# schaltplan.net
KiCad netlist of a schematic drawn in EAGLE
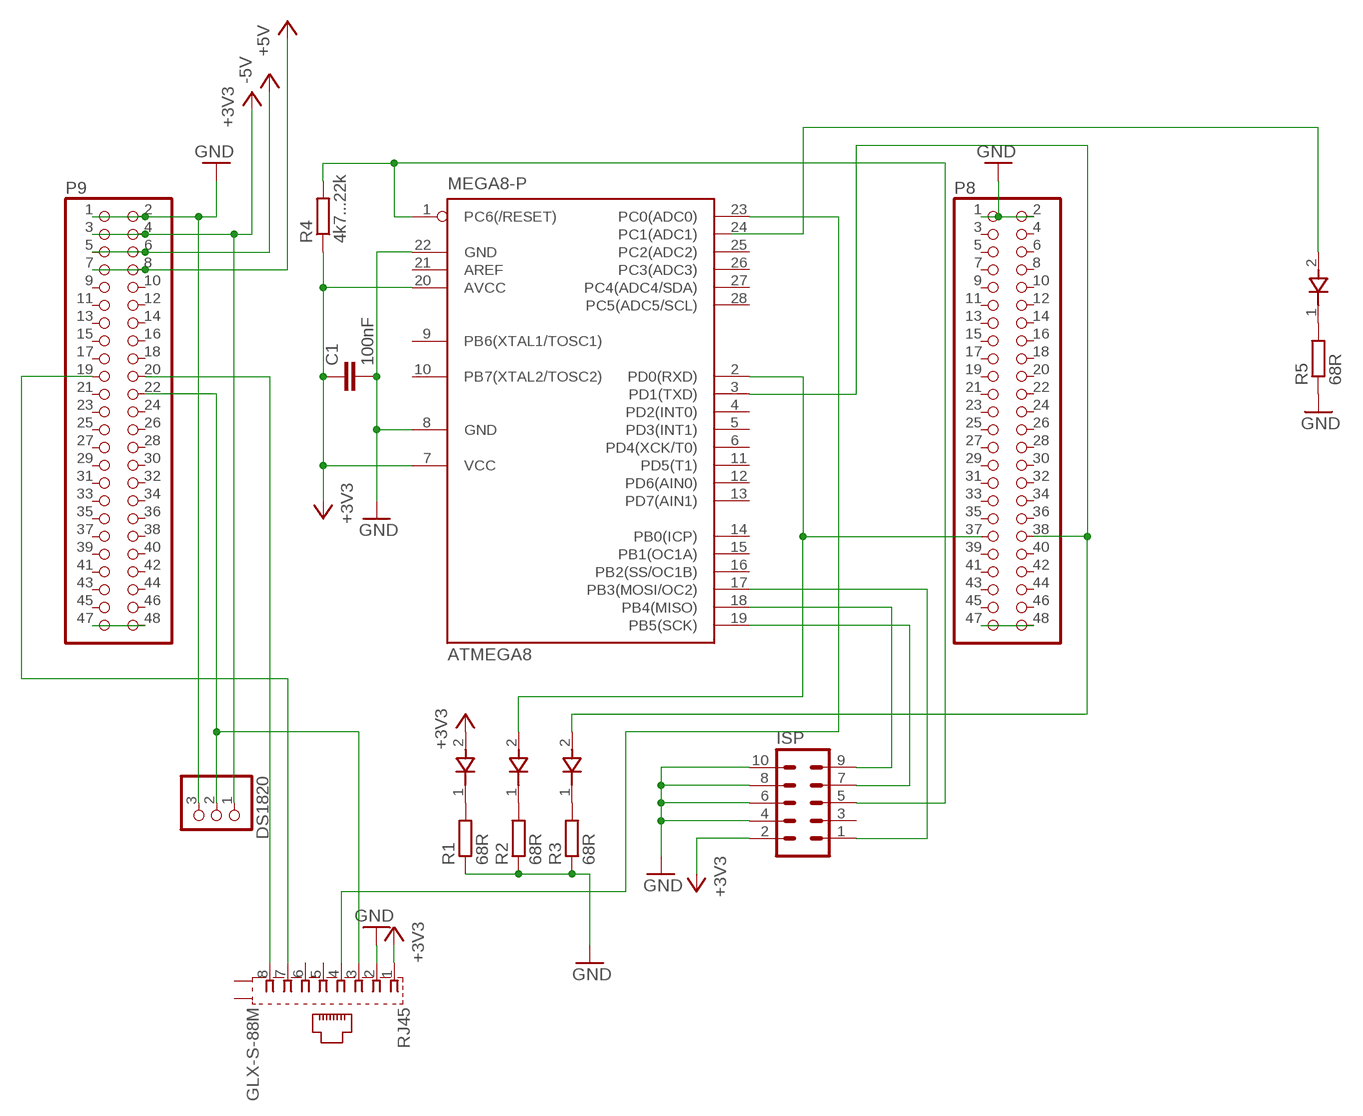
[diagram p0: schematic, sheet 1]

(export (version "E")
  (design (tool "Eeschema 10.0.6"))
  (components
    (comp (ref "ATMEGA8")
      (value "MEGA8-P")
      (footprint "eagle-import:DIL28-3")
      (libsource (lib "eagle-import") (part "MEGA8-P"))
    )
    (comp (ref "C1")
      (value "100nF")
      (footprint "eagle-import:C0805")
      (libsource (lib "eagle-import") (part "C-EUC0805"))
    )
    (comp (ref "DS1820")
      (value "PINHD-1X3")
      (footprint "eagle-import:1X03")
      (libsource (lib "eagle-import") (part "PINHD-1X3"))
    )
    (comp (ref "ISP")
      (value "ML10")
      (footprint "eagle-import:ML10")
      (libsource (lib "eagle-import") (part "ML10"))
    )
    (comp (ref "P8")
      (value "PINHD-2X24")
      (footprint "eagle-import:2X24")
      (libsource (lib "eagle-import") (part "PINHD-2X24"))
    )
    (comp (ref "P9")
      (value "PINHD-2X24")
      (footprint "eagle-import:2X24")
      (libsource (lib "eagle-import") (part "PINHD-2X24"))
    )
    (comp (ref "R1")
      (value "68R")
      (footprint "eagle-import:R1206")
      (libsource (lib "eagle-import") (part "R-EU_R1206"))
    )
    (comp (ref "R2")
      (value "68R")
      (footprint "eagle-import:R1206")
      (libsource (lib "eagle-import") (part "R-EU_R1206"))
    )
    (comp (ref "R3")
      (value "68R")
      (footprint "eagle-import:R1206")
      (libsource (lib "eagle-import") (part "R-EU_R1206"))
    )
    (comp (ref "R4")
      (value "4k7...22k")
      (footprint "eagle-import:R1206")
      (libsource (lib "eagle-import") (part "R-EU_R1206"))
    )
    (comp (ref "R5")
      (value "68R")
      (footprint "eagle-import:R1206")
      (libsource (lib "eagle-import") (part "R-EU_R1206"))
    )
    (comp (ref "RJ45")
      (value "GLX-S-88M")
      (footprint "eagle-import:GLX-S-88M")
      (libsource (lib "eagle-import") (part "GLX-S-88M"))
    )
    (comp (ref "U$1")
      (value "LOL_LED")
      (footprint "eagle-import:LOL_LED")
      (libsource (lib "eagle-import") (part "LOL_LED"))
    )
    (comp (ref "U$2")
      (value "LOL_LED")
      (footprint "eagle-import:LOL_LED")
      (libsource (lib "eagle-import") (part "LOL_LED"))
    )
    (comp (ref "U$3")
      (value "LOL_LED")
      (footprint "eagle-import:LOL_LED")
      (libsource (lib "eagle-import") (part "LOL_LED"))
    )
    (comp (ref "U$4")
      (value "LOL_LED")
      (footprint "eagle-import:LOL_LED")
      (libsource (lib "eagle-import") (part "LOL_LED"))
    )
  )
  (nets
    (net (code "1") (name "+3V3") (class "Default")
      (node (ref "ATMEGA8") (pin "20") (pinfunction "AVCC_20") (pintype "power_in"))
      (node (ref "ATMEGA8") (pin "7") (pinfunction "VCC_7") (pintype "power_in"))
      (node (ref "C1") (pin "1") (pinfunction "1_1") (pintype "passive"))
      (node (ref "DS1820") (pin "1") (pinfunction "1_1") (pintype "passive"))
      (node (ref "ISP") (pin "2") (pinfunction "2_2") (pintype "passive"))
      (node (ref "P9") (pin "3") (pinfunction "3_3") (pintype "passive"))
      (node (ref "P9") (pin "4") (pinfunction "4_4") (pintype "passive"))
      (node (ref "R4") (pin "1") (pinfunction "1_1") (pintype "passive"))
      (node (ref "RJ45") (pin "1") (pinfunction "1_1") (pintype "passive"))
      (node (ref "U$1") (pin "2") (pinfunction "POS_2") (pintype "bidirectional"))
    )
    (net (code "2") (name "+5V") (class "Default")
      (node (ref "P9") (pin "7") (pinfunction "7_7") (pintype "passive"))
      (node (ref "P9") (pin "8") (pinfunction "8_8") (pintype "passive"))
    )
    (net (code "3") (name "-5V") (class "Default")
      (node (ref "P9") (pin "5") (pinfunction "5_5") (pintype "passive"))
      (node (ref "P9") (pin "6") (pinfunction "6_6") (pintype "passive"))
    )
    (net (code "4") (name "/FILL") (class "Default")
      (node (ref "P8") (pin "47") (pinfunction "47_47") (pintype "passive"))
      (node (ref "P8") (pin "48") (pinfunction "48_48") (pintype "passive"))
      (node (ref "P9") (pin "47") (pinfunction "47_47") (pintype "passive"))
      (node (ref "P9") (pin "48") (pinfunction "48_48") (pintype "passive"))
    )
    (net (code "5") (name "GND") (class "Default")
      (node (ref "ATMEGA8") (pin "22") (pinfunction "GND_22") (pintype "power_in"))
      (node (ref "ATMEGA8") (pin "8") (pinfunction "GND_8") (pintype "power_in"))
      (node (ref "C1") (pin "2") (pinfunction "2_2") (pintype "passive"))
      (node (ref "DS1820") (pin "3") (pinfunction "3_3") (pintype "passive"))
      (node (ref "ISP") (pin "10") (pinfunction "10_10") (pintype "passive"))
      (node (ref "ISP") (pin "4") (pinfunction "4_4") (pintype "passive"))
      (node (ref "ISP") (pin "6") (pinfunction "6_6") (pintype "passive"))
      (node (ref "ISP") (pin "8") (pinfunction "8_8") (pintype "passive"))
      (node (ref "P8") (pin "1") (pinfunction "1_1") (pintype "passive"))
      (node (ref "P8") (pin "2") (pinfunction "2_2") (pintype "passive"))
      (node (ref "P9") (pin "1") (pinfunction "1_1") (pintype "passive"))
      (node (ref "P9") (pin "2") (pinfunction "2_2") (pintype "passive"))
      (node (ref "R1") (pin "1") (pinfunction "1_1") (pintype "passive"))
      (node (ref "R2") (pin "1") (pinfunction "1_1") (pintype "passive"))
      (node (ref "R3") (pin "1") (pinfunction "1_1") (pintype "passive"))
      (node (ref "R5") (pin "1") (pinfunction "1_1") (pintype "passive"))
      (node (ref "RJ45") (pin "2") (pinfunction "2_2") (pintype "passive"))
    )
    (net (code "6") (name "Net-(ATMEGA8-PB3(MOSI{slash}OC2))") (class "Default")
      (node (ref "ATMEGA8") (pin "17") (pinfunction "PB3(MOSI/OC2)_17") (pintype "bidirectional"))
      (node (ref "ISP") (pin "1") (pinfunction "1_1") (pintype "passive"))
    )
    (net (code "7") (name "Net-(ATMEGA8-PB4(MISO))") (class "Default")
      (node (ref "ATMEGA8") (pin "18") (pinfunction "PB4(MISO)_18") (pintype "bidirectional"))
      (node (ref "ISP") (pin "9") (pinfunction "9_9") (pintype "passive"))
    )
    (net (code "8") (name "Net-(ATMEGA8-PB5(SCK))") (class "Default")
      (node (ref "ATMEGA8") (pin "19") (pinfunction "PB5(SCK)_19") (pintype "bidirectional"))
      (node (ref "ISP") (pin "7") (pinfunction "7_7") (pintype "passive"))
    )
    (net (code "9") (name "Net-(ATMEGA8-PC0(ADC0))") (class "Default")
      (node (ref "ATMEGA8") (pin "23") (pinfunction "PC0(ADC0)_23") (pintype "bidirectional"))
      (node (ref "RJ45") (pin "4") (pinfunction "4_4") (pintype "passive"))
    )
    (net (code "10") (name "Net-(ATMEGA8-PC6({slash}RESET))") (class "Default")
      (node (ref "ATMEGA8") (pin "1") (pinfunction "PC6(/RESET)_1") (pintype "bidirectional"))
      (node (ref "ISP") (pin "5") (pinfunction "5_5") (pintype "passive"))
      (node (ref "R4") (pin "2") (pinfunction "2_2") (pintype "passive"))
    )
    (net (code "11") (name "Net-(ATMEGA8-PD0(RXD))") (class "Default")
      (node (ref "ATMEGA8") (pin "2") (pinfunction "PD0(RXD)_2") (pintype "bidirectional"))
      (node (ref "P8") (pin "37") (pinfunction "37_37") (pintype "passive"))
      (node (ref "U$2") (pin "2") (pinfunction "POS_2") (pintype "bidirectional"))
    )
    (net (code "12") (name "Net-(ATMEGA8-PD1(TXD))") (class "Default")
      (node (ref "ATMEGA8") (pin "3") (pinfunction "PD1(TXD)_3") (pintype "bidirectional"))
      (node (ref "P8") (pin "38") (pinfunction "38_38") (pintype "passive"))
      (node (ref "U$3") (pin "2") (pinfunction "POS_2") (pintype "bidirectional"))
    )
    (net (code "13") (name "Net-(DS1820-Pad2)") (class "Default")
      (node (ref "DS1820") (pin "2") (pinfunction "2_2") (pintype "passive"))
      (node (ref "P9") (pin "22") (pinfunction "22_22") (pintype "passive"))
      (node (ref "RJ45") (pin "3") (pinfunction "3_3") (pintype "passive"))
    )
    (net (code "14") (name "Net-(P9-Pad19)") (class "Default")
      (node (ref "P9") (pin "19") (pinfunction "19_19") (pintype "passive"))
      (node (ref "RJ45") (pin "7") (pinfunction "7_7") (pintype "passive"))
    )
    (net (code "15") (name "Net-(P9-Pad20)") (class "Default")
      (node (ref "P9") (pin "20") (pinfunction "20_20") (pintype "passive"))
      (node (ref "RJ45") (pin "8") (pinfunction "8_8") (pintype "passive"))
    )
    (net (code "16") (name "Net-(U$1-NEG)") (class "Default")
      (node (ref "R1") (pin "2") (pinfunction "2_2") (pintype "passive"))
      (node (ref "U$1") (pin "1") (pinfunction "NEG_1") (pintype "bidirectional"))
    )
    (net (code "17") (name "Net-(U$2-NEG)") (class "Default")
      (node (ref "R2") (pin "2") (pinfunction "2_2") (pintype "passive"))
      (node (ref "U$2") (pin "1") (pinfunction "NEG_1") (pintype "bidirectional"))
    )
    (net (code "18") (name "Net-(U$3-NEG)") (class "Default")
      (node (ref "R3") (pin "2") (pinfunction "2_2") (pintype "passive"))
      (node (ref "U$3") (pin "1") (pinfunction "NEG_1") (pintype "bidirectional"))
    )
    (net (code "19") (name "Net-(U$4-NEG)") (class "Default")
      (node (ref "R5") (pin "2") (pinfunction "2_2") (pintype "passive"))
      (node (ref "U$4") (pin "1") (pinfunction "NEG_1") (pintype "bidirectional"))
    )
    (net (code "20") (name "unconnected-(ATMEGA8-AREF-Pad21)") (class "Default")
      (node (ref "ATMEGA8") (pin "21") (pinfunction "AREF_21") (pintype "passive"))
    )
    (net (code "21") (name "unconnected-(ATMEGA8-PB0(ICP)-Pad14)") (class "Default")
      (node (ref "ATMEGA8") (pin "14") (pinfunction "PB0(ICP)_14") (pintype "bidirectional"))
    )
    (net (code "22") (name "unconnected-(ATMEGA8-PB1(OC1A)-Pad15)") (class "Default")
      (node (ref "ATMEGA8") (pin "15") (pinfunction "PB1(OC1A)_15") (pintype "bidirectional"))
    )
    (net (code "23") (name "unconnected-(ATMEGA8-PB2(SS{slash}OC1B)-Pad16)") (class "Default")
      (node (ref "ATMEGA8") (pin "16") (pinfunction "PB2(SS/OC1B)_16") (pintype "bidirectional"))
    )
    (net (code "24") (name "unconnected-(ATMEGA8-PB6(XTAL1{slash}TOSC1)-Pad9)") (class "Default")
      (node (ref "ATMEGA8") (pin "9") (pinfunction "PB6(XTAL1/TOSC1)_9") (pintype "bidirectional"))
    )
    (net (code "25") (name "unconnected-(ATMEGA8-PB7(XTAL2{slash}TOSC2)-Pad10)") (class "Default")
      (node (ref "ATMEGA8") (pin "10") (pinfunction "PB7(XTAL2/TOSC2)_10") (pintype "bidirectional"))
    )
    (net (code "26") (name "unconnected-(ATMEGA8-PC1(ADC1)-Pad24)") (class "Default")
      (node (ref "ATMEGA8") (pin "24") (pinfunction "PC1(ADC1)_24") (pintype "bidirectional"))
    )
    (net (code "27") (name "unconnected-(ATMEGA8-PC2(ADC2)-Pad25)") (class "Default")
      (node (ref "ATMEGA8") (pin "25") (pinfunction "PC2(ADC2)_25") (pintype "bidirectional"))
    )
    (net (code "28") (name "unconnected-(ATMEGA8-PC3(ADC3)-Pad26)") (class "Default")
      (node (ref "ATMEGA8") (pin "26") (pinfunction "PC3(ADC3)_26") (pintype "bidirectional"))
    )
    (net (code "29") (name "unconnected-(ATMEGA8-PC4(ADC4{slash}SDA)-Pad27)") (class "Default")
      (node (ref "ATMEGA8") (pin "27") (pinfunction "PC4(ADC4/SDA)_27") (pintype "bidirectional"))
    )
    (net (code "30") (name "unconnected-(ATMEGA8-PC5(ADC5{slash}SCL)-Pad28)") (class "Default")
      (node (ref "ATMEGA8") (pin "28") (pinfunction "PC5(ADC5/SCL)_28") (pintype "bidirectional"))
    )
    (net (code "31") (name "unconnected-(ATMEGA8-PD2(INT0)-Pad4)") (class "Default")
      (node (ref "ATMEGA8") (pin "4") (pinfunction "PD2(INT0)_4") (pintype "bidirectional"))
    )
    (net (code "32") (name "unconnected-(ATMEGA8-PD3(INT1)-Pad5)") (class "Default")
      (node (ref "ATMEGA8") (pin "5") (pinfunction "PD3(INT1)_5") (pintype "bidirectional"))
    )
    (net (code "33") (name "unconnected-(ATMEGA8-PD4(XCK{slash}T0)-Pad6)") (class "Default")
      (node (ref "ATMEGA8") (pin "6") (pinfunction "PD4(XCK/T0)_6") (pintype "bidirectional"))
    )
    (net (code "34") (name "unconnected-(ATMEGA8-PD5(T1)-Pad11)") (class "Default")
      (node (ref "ATMEGA8") (pin "11") (pinfunction "PD5(T1)_11") (pintype "bidirectional"))
    )
    (net (code "35") (name "unconnected-(ATMEGA8-PD6(AIN0)-Pad12)") (class "Default")
      (node (ref "ATMEGA8") (pin "12") (pinfunction "PD6(AIN0)_12") (pintype "bidirectional"))
    )
    (net (code "36") (name "unconnected-(ATMEGA8-PD7(AIN1)-Pad13)") (class "Default")
      (node (ref "ATMEGA8") (pin "13") (pinfunction "PD7(AIN1)_13") (pintype "bidirectional"))
    )
    (net (code "37") (name "unconnected-(ISP-Pad3)") (class "Default")
      (node (ref "ISP") (pin "3") (pinfunction "3_3") (pintype "passive"))
    )
    (net (code "38") (name "unconnected-(P8-Pad3)") (class "Default")
      (node (ref "P8") (pin "3") (pinfunction "3_3") (pintype "passive"))
    )
    (net (code "39") (name "unconnected-(P8-Pad4)") (class "Default")
      (node (ref "P8") (pin "4") (pinfunction "4_4") (pintype "passive"))
    )
    (net (code "40") (name "unconnected-(P8-Pad5)") (class "Default")
      (node (ref "P8") (pin "5") (pinfunction "5_5") (pintype "passive"))
    )
    (net (code "41") (name "unconnected-(P8-Pad6)") (class "Default")
      (node (ref "P8") (pin "6") (pinfunction "6_6") (pintype "passive"))
    )
    (net (code "42") (name "unconnected-(P8-Pad7)") (class "Default")
      (node (ref "P8") (pin "7") (pinfunction "7_7") (pintype "passive"))
    )
    (net (code "43") (name "unconnected-(P8-Pad8)") (class "Default")
      (node (ref "P8") (pin "8") (pinfunction "8_8") (pintype "passive"))
    )
    (net (code "44") (name "unconnected-(P8-Pad9)") (class "Default")
      (node (ref "P8") (pin "9") (pinfunction "9_9") (pintype "passive"))
    )
    (net (code "45") (name "unconnected-(P8-Pad10)") (class "Default")
      (node (ref "P8") (pin "10") (pinfunction "10_10") (pintype "passive"))
    )
    (net (code "46") (name "unconnected-(P8-Pad11)") (class "Default")
      (node (ref "P8") (pin "11") (pinfunction "11_11") (pintype "passive"))
    )
    (net (code "47") (name "unconnected-(P8-Pad12)") (class "Default")
      (node (ref "P8") (pin "12") (pinfunction "12_12") (pintype "passive"))
    )
    (net (code "48") (name "unconnected-(P8-Pad13)") (class "Default")
      (node (ref "P8") (pin "13") (pinfunction "13_13") (pintype "passive"))
    )
    (net (code "49") (name "unconnected-(P8-Pad14)") (class "Default")
      (node (ref "P8") (pin "14") (pinfunction "14_14") (pintype "passive"))
    )
    (net (code "50") (name "unconnected-(P8-Pad15)") (class "Default")
      (node (ref "P8") (pin "15") (pinfunction "15_15") (pintype "passive"))
    )
    (net (code "51") (name "unconnected-(P8-Pad16)") (class "Default")
      (node (ref "P8") (pin "16") (pinfunction "16_16") (pintype "passive"))
    )
    (net (code "52") (name "unconnected-(P8-Pad17)") (class "Default")
      (node (ref "P8") (pin "17") (pinfunction "17_17") (pintype "passive"))
    )
    (net (code "53") (name "unconnected-(P8-Pad18)") (class "Default")
      (node (ref "P8") (pin "18") (pinfunction "18_18") (pintype "passive"))
    )
    (net (code "54") (name "unconnected-(P8-Pad19)") (class "Default")
      (node (ref "P8") (pin "19") (pinfunction "19_19") (pintype "passive"))
    )
    (net (code "55") (name "unconnected-(P8-Pad20)") (class "Default")
      (node (ref "P8") (pin "20") (pinfunction "20_20") (pintype "passive"))
    )
    (net (code "56") (name "unconnected-(P8-Pad21)") (class "Default")
      (node (ref "P8") (pin "21") (pinfunction "21_21") (pintype "passive"))
    )
    (net (code "57") (name "unconnected-(P8-Pad22)") (class "Default")
      (node (ref "P8") (pin "22") (pinfunction "22_22") (pintype "passive"))
    )
    (net (code "58") (name "unconnected-(P8-Pad23)") (class "Default")
      (node (ref "P8") (pin "23") (pinfunction "23_23") (pintype "passive"))
    )
    (net (code "59") (name "unconnected-(P8-Pad24)") (class "Default")
      (node (ref "P8") (pin "24") (pinfunction "24_24") (pintype "passive"))
    )
    (net (code "60") (name "unconnected-(P8-Pad25)") (class "Default")
      (node (ref "P8") (pin "25") (pinfunction "25_25") (pintype "passive"))
    )
    (net (code "61") (name "unconnected-(P8-Pad26)") (class "Default")
      (node (ref "P8") (pin "26") (pinfunction "26_26") (pintype "passive"))
    )
    (net (code "62") (name "unconnected-(P8-Pad27)") (class "Default")
      (node (ref "P8") (pin "27") (pinfunction "27_27") (pintype "passive"))
    )
    (net (code "63") (name "unconnected-(P8-Pad28)") (class "Default")
      (node (ref "P8") (pin "28") (pinfunction "28_28") (pintype "passive"))
    )
    (net (code "64") (name "unconnected-(P8-Pad29)") (class "Default")
      (node (ref "P8") (pin "29") (pinfunction "29_29") (pintype "passive"))
    )
    (net (code "65") (name "unconnected-(P8-Pad30)") (class "Default")
      (node (ref "P8") (pin "30") (pinfunction "30_30") (pintype "passive"))
    )
    (net (code "66") (name "unconnected-(P8-Pad31)") (class "Default")
      (node (ref "P8") (pin "31") (pinfunction "31_31") (pintype "passive"))
    )
    (net (code "67") (name "unconnected-(P8-Pad32)") (class "Default")
      (node (ref "P8") (pin "32") (pinfunction "32_32") (pintype "passive"))
    )
    (net (code "68") (name "unconnected-(P8-Pad33)") (class "Default")
      (node (ref "P8") (pin "33") (pinfunction "33_33") (pintype "passive"))
    )
    (net (code "69") (name "unconnected-(P8-Pad34)") (class "Default")
      (node (ref "P8") (pin "34") (pinfunction "34_34") (pintype "passive"))
    )
    (net (code "70") (name "unconnected-(P8-Pad35)") (class "Default")
      (node (ref "P8") (pin "35") (pinfunction "35_35") (pintype "passive"))
    )
    (net (code "71") (name "unconnected-(P8-Pad36)") (class "Default")
      (node (ref "P8") (pin "36") (pinfunction "36_36") (pintype "passive"))
    )
    (net (code "72") (name "unconnected-(P8-Pad39)") (class "Default")
      (node (ref "P8") (pin "39") (pinfunction "39_39") (pintype "passive"))
    )
    (net (code "73") (name "unconnected-(P8-Pad40)") (class "Default")
      (node (ref "P8") (pin "40") (pinfunction "40_40") (pintype "passive"))
    )
    (net (code "74") (name "unconnected-(P8-Pad41)") (class "Default")
      (node (ref "P8") (pin "41") (pinfunction "41_41") (pintype "passive"))
    )
    (net (code "75") (name "unconnected-(P8-Pad42)") (class "Default")
      (node (ref "P8") (pin "42") (pinfunction "42_42") (pintype "passive"))
    )
    (net (code "76") (name "unconnected-(P8-Pad43)") (class "Default")
      (node (ref "P8") (pin "43") (pinfunction "43_43") (pintype "passive"))
    )
    (net (code "77") (name "unconnected-(P8-Pad44)") (class "Default")
      (node (ref "P8") (pin "44") (pinfunction "44_44") (pintype "passive"))
    )
    (net (code "78") (name "unconnected-(P8-Pad45)") (class "Default")
      (node (ref "P8") (pin "45") (pinfunction "45_45") (pintype "passive"))
    )
    (net (code "79") (name "unconnected-(P8-Pad46)") (class "Default")
      (node (ref "P8") (pin "46") (pinfunction "46_46") (pintype "passive"))
    )
    (net (code "80") (name "unconnected-(P9-Pad9)") (class "Default")
      (node (ref "P9") (pin "9") (pinfunction "9_9") (pintype "passive"))
    )
    (net (code "81") (name "unconnected-(P9-Pad10)") (class "Default")
      (node (ref "P9") (pin "10") (pinfunction "10_10") (pintype "passive"))
    )
    (net (code "82") (name "unconnected-(P9-Pad11)") (class "Default")
      (node (ref "P9") (pin "11") (pinfunction "11_11") (pintype "passive"))
    )
    (net (code "83") (name "unconnected-(P9-Pad12)") (class "Default")
      (node (ref "P9") (pin "12") (pinfunction "12_12") (pintype "passive"))
    )
    (net (code "84") (name "unconnected-(P9-Pad13)") (class "Default")
      (node (ref "P9") (pin "13") (pinfunction "13_13") (pintype "passive"))
    )
    (net (code "85") (name "unconnected-(P9-Pad14)") (class "Default")
      (node (ref "P9") (pin "14") (pinfunction "14_14") (pintype "passive"))
    )
    (net (code "86") (name "unconnected-(P9-Pad15)") (class "Default")
      (node (ref "P9") (pin "15") (pinfunction "15_15") (pintype "passive"))
    )
    (net (code "87") (name "unconnected-(P9-Pad16)") (class "Default")
      (node (ref "P9") (pin "16") (pinfunction "16_16") (pintype "passive"))
    )
    (net (code "88") (name "unconnected-(P9-Pad17)") (class "Default")
      (node (ref "P9") (pin "17") (pinfunction "17_17") (pintype "passive"))
    )
    (net (code "89") (name "unconnected-(P9-Pad18)") (class "Default")
      (node (ref "P9") (pin "18") (pinfunction "18_18") (pintype "passive"))
    )
    (net (code "90") (name "unconnected-(P9-Pad21)") (class "Default")
      (node (ref "P9") (pin "21") (pinfunction "21_21") (pintype "passive"))
    )
    (net (code "91") (name "unconnected-(P9-Pad23)") (class "Default")
      (node (ref "P9") (pin "23") (pinfunction "23_23") (pintype "passive"))
    )
    (net (code "92") (name "unconnected-(P9-Pad24)") (class "Default")
      (node (ref "P9") (pin "24") (pinfunction "24_24") (pintype "passive"))
    )
    (net (code "93") (name "unconnected-(P9-Pad25)") (class "Default")
      (node (ref "P9") (pin "25") (pinfunction "25_25") (pintype "passive"))
    )
    (net (code "94") (name "unconnected-(P9-Pad26)") (class "Default")
      (node (ref "P9") (pin "26") (pinfunction "26_26") (pintype "passive"))
    )
    (net (code "95") (name "unconnected-(P9-Pad27)") (class "Default")
      (node (ref "P9") (pin "27") (pinfunction "27_27") (pintype "passive"))
    )
    (net (code "96") (name "unconnected-(P9-Pad28)") (class "Default")
      (node (ref "P9") (pin "28") (pinfunction "28_28") (pintype "passive"))
    )
    (net (code "97") (name "unconnected-(P9-Pad29)") (class "Default")
      (node (ref "P9") (pin "29") (pinfunction "29_29") (pintype "passive"))
    )
    (net (code "98") (name "unconnected-(P9-Pad30)") (class "Default")
      (node (ref "P9") (pin "30") (pinfunction "30_30") (pintype "passive"))
    )
    (net (code "99") (name "unconnected-(P9-Pad31)") (class "Default")
      (node (ref "P9") (pin "31") (pinfunction "31_31") (pintype "passive"))
    )
    (net (code "100") (name "unconnected-(P9-Pad32)") (class "Default")
      (node (ref "P9") (pin "32") (pinfunction "32_32") (pintype "passive"))
    )
    (net (code "101") (name "unconnected-(P9-Pad33)") (class "Default")
      (node (ref "P9") (pin "33") (pinfunction "33_33") (pintype "passive"))
    )
    (net (code "102") (name "unconnected-(P9-Pad34)") (class "Default")
      (node (ref "P9") (pin "34") (pinfunction "34_34") (pintype "passive"))
    )
    (net (code "103") (name "unconnected-(P9-Pad35)") (class "Default")
      (node (ref "P9") (pin "35") (pinfunction "35_35") (pintype "passive"))
    )
    (net (code "104") (name "unconnected-(P9-Pad36)") (class "Default")
      (node (ref "P9") (pin "36") (pinfunction "36_36") (pintype "passive"))
    )
    (net (code "105") (name "unconnected-(P9-Pad37)") (class "Default")
      (node (ref "P9") (pin "37") (pinfunction "37_37") (pintype "passive"))
    )
    (net (code "106") (name "unconnected-(P9-Pad38)") (class "Default")
      (node (ref "P9") (pin "38") (pinfunction "38_38") (pintype "passive"))
    )
    (net (code "107") (name "unconnected-(P9-Pad39)") (class "Default")
      (node (ref "P9") (pin "39") (pinfunction "39_39") (pintype "passive"))
    )
    (net (code "108") (name "unconnected-(P9-Pad40)") (class "Default")
      (node (ref "P9") (pin "40") (pinfunction "40_40") (pintype "passive"))
    )
    (net (code "109") (name "unconnected-(P9-Pad41)") (class "Default")
      (node (ref "P9") (pin "41") (pinfunction "41_41") (pintype "passive"))
    )
    (net (code "110") (name "unconnected-(P9-Pad42)") (class "Default")
      (node (ref "P9") (pin "42") (pinfunction "42_42") (pintype "passive"))
    )
    (net (code "111") (name "unconnected-(P9-Pad43)") (class "Default")
      (node (ref "P9") (pin "43") (pinfunction "43_43") (pintype "passive"))
    )
    (net (code "112") (name "unconnected-(P9-Pad44)") (class "Default")
      (node (ref "P9") (pin "44") (pinfunction "44_44") (pintype "passive"))
    )
    (net (code "113") (name "unconnected-(P9-Pad45)") (class "Default")
      (node (ref "P9") (pin "45") (pinfunction "45_45") (pintype "passive"))
    )
    (net (code "114") (name "unconnected-(P9-Pad46)") (class "Default")
      (node (ref "P9") (pin "46") (pinfunction "46_46") (pintype "passive"))
    )
    (net (code "115") (name "unconnected-(RJ45-Pad5)") (class "Default")
      (node (ref "RJ45") (pin "5") (pinfunction "5_5") (pintype "passive"))
    )
    (net (code "116") (name "unconnected-(RJ45-Pad6)") (class "Default")
      (node (ref "RJ45") (pin "6") (pinfunction "6_6") (pintype "passive"))
    )
    (net (code "117") (name "unconnected-(RJ45-PadS1)") (class "Default")
      (node (ref "RJ45") (pin "S1") (pinfunction "S1_S1") (pintype "passive"))
    )
    (net (code "118") (name "unconnected-(RJ45-PadS2)") (class "Default")
      (node (ref "RJ45") (pin "S2") (pinfunction "S2_S2") (pintype "passive"))
    )
    (net (code "119") (name "unconnected-(U$4-POS-Pad2)") (class "Default")
      (node (ref "U$4") (pin "2") (pinfunction "POS_2") (pintype "bidirectional"))
    )
  )
)
